# mcp3008_rpi_Dirty_july_2015.net
KiCad netlist of a schematic drawn in EAGLE
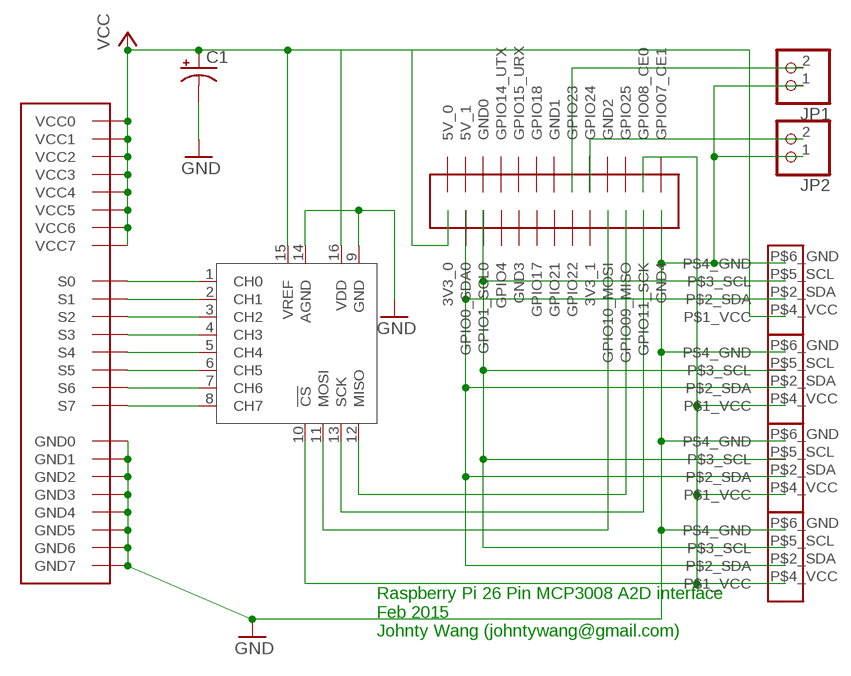
[diagram p0: schematic, sheet 1]

(export (version "E")
  (design (tool "Eeschema 10.0.6"))
  (components
    (comp (ref "C1")
      (value "CPOL-USE2.5-6")
      (footprint "eagle-import:E2,5-6")
      (libsource (lib "eagle-import") (part "CPOL-USE2.5-6"))
    )
    (comp (ref "JP1")
      (value "PINHD-1X2")
      (footprint "eagle-import:1X02")
      (libsource (lib "eagle-import") (part "PINHD-1X2"))
    )
    (comp (ref "JP2")
      (value "PINHD-1X2")
      (footprint "eagle-import:1X02")
      (libsource (lib "eagle-import") (part "PINHD-1X2"))
    )
    (comp (ref "U$1")
      (value "3BY83X8_SAMTEC")
      (footprint "eagle-import:3X8_PKG")
      (libsource (lib "eagle-import") (part "3BY83X8_SAMTEC"))
    )
    (comp (ref "U$2")
      (value "RPI_26")
      (footprint "eagle-import:RPI26")
      (libsource (lib "eagle-import") (part "RPI_26"))
    )
    (comp (ref "U$3")
      (value "MCP3008P")
      (footprint "eagle-import:DIL16")
      (libsource (lib "eagle-import") (part "MCP3008P"))
    )
    (comp (ref "U$4")
      (value "ICUBE_I2C")
      (footprint "eagle-import:2X3")
      (libsource (lib "eagle-import") (part "ICUBE_I2C"))
    )
    (comp (ref "U$5")
      (value "ICUBE_I2C")
      (footprint "eagle-import:2X3")
      (libsource (lib "eagle-import") (part "ICUBE_I2C"))
    )
    (comp (ref "U$6")
      (value "ICUBE_I2C")
      (footprint "eagle-import:2X3")
      (libsource (lib "eagle-import") (part "ICUBE_I2C"))
    )
    (comp (ref "U$7")
      (value "ICUBE_I2C")
      (footprint "eagle-import:2X3")
      (libsource (lib "eagle-import") (part "ICUBE_I2C"))
    )
  )
  (nets
    (net (code "1") (name "/5V_0") (class "Default")
      (node (ref "U$2") (pin "5V0") (pinfunction "5V_0_5V0") (pintype "power_in"))
    )
    (net (code "2") (name "GND") (class "Default")
      (node (ref "C1") (pin "-") (pinfunction "-_-") (pintype "passive"))
      (node (ref "JP1") (pin "1") (pinfunction "1_1") (pintype "passive"))
      (node (ref "JP2") (pin "1") (pinfunction "1_1") (pintype "passive"))
      (node (ref "U$1") (pin "GND0") (pinfunction "GND0_GND0") (pintype "bidirectional"))
      (node (ref "U$1") (pin "GND1") (pinfunction "GND1_GND1") (pintype "bidirectional"))
      (node (ref "U$1") (pin "GND2") (pinfunction "GND2_GND2") (pintype "bidirectional"))
      (node (ref "U$1") (pin "GND3") (pinfunction "GND3_GND3") (pintype "bidirectional"))
      (node (ref "U$1") (pin "GND4") (pinfunction "GND4_GND4") (pintype "bidirectional"))
      (node (ref "U$1") (pin "GND5") (pinfunction "GND5_GND5") (pintype "bidirectional"))
      (node (ref "U$1") (pin "GND6") (pinfunction "GND6_GND6") (pintype "bidirectional"))
      (node (ref "U$1") (pin "GND7") (pinfunction "GND7_GND7") (pintype "bidirectional"))
      (node (ref "U$2") (pin "GND4") (pinfunction "GND4_GND4") (pintype "bidirectional"))
      (node (ref "U$3") (pin "14") (pinfunction "AGND_14") (pintype "power_in"))
      (node (ref "U$3") (pin "9") (pinfunction "GND_9") (pintype "power_in"))
      (node (ref "U$4") (pin "P$6_GND") (pinfunction "P$4_GND_P$6_GND") (pintype "bidirectional"))
      (node (ref "U$5") (pin "P$6_GND") (pinfunction "P$4_GND_P$6_GND") (pintype "bidirectional"))
      (node (ref "U$6") (pin "P$6_GND") (pinfunction "P$4_GND_P$6_GND") (pintype "bidirectional"))
      (node (ref "U$7") (pin "P$6_GND") (pinfunction "P$4_GND_P$6_GND") (pintype "bidirectional"))
    )
    (net (code "3") (name "Net-(JP1-Pad2)") (class "Default")
      (node (ref "JP1") (pin "2") (pinfunction "2_2") (pintype "passive"))
      (node (ref "U$2") (pin "GPIO23") (pinfunction "GPIO23_GPIO23") (pintype "bidirectional"))
    )
    (net (code "4") (name "Net-(JP2-Pad2)") (class "Default")
      (node (ref "JP2") (pin "2") (pinfunction "2_2") (pintype "passive"))
      (node (ref "U$2") (pin "GPIO24") (pinfunction "GPIO24_GPIO24") (pintype "bidirectional"))
    )
    (net (code "5") (name "Net-(U$2-GPIO0_SDA0)") (class "Default")
      (node (ref "U$2") (pin "GPIO0") (pinfunction "GPIO0_SDA0_GPIO0") (pintype "bidirectional"))
      (node (ref "U$4") (pin "P$2_SDA") (pinfunction "P$2_SDA_P$2_SDA") (pintype "bidirectional"))
      (node (ref "U$5") (pin "P$2_SDA") (pinfunction "P$2_SDA_P$2_SDA") (pintype "bidirectional"))
      (node (ref "U$6") (pin "P$2_SDA") (pinfunction "P$2_SDA_P$2_SDA") (pintype "bidirectional"))
      (node (ref "U$7") (pin "P$2_SDA") (pinfunction "P$2_SDA_P$2_SDA") (pintype "bidirectional"))
    )
    (net (code "6") (name "Net-(U$2-GPIO1_SCL0)") (class "Default")
      (node (ref "U$2") (pin "GPIO01") (pinfunction "GPIO1_SCL0_GPIO01") (pintype "bidirectional"))
      (node (ref "U$4") (pin "P$5_SCL") (pinfunction "P$3_SCL_P$5_SCL") (pintype "bidirectional"))
      (node (ref "U$5") (pin "P$5_SCL") (pinfunction "P$3_SCL_P$5_SCL") (pintype "bidirectional"))
      (node (ref "U$6") (pin "P$5_SCL") (pinfunction "P$3_SCL_P$5_SCL") (pintype "bidirectional"))
      (node (ref "U$7") (pin "P$5_SCL") (pinfunction "P$3_SCL_P$5_SCL") (pintype "bidirectional"))
    )
    (net (code "7") (name "Net-(U$2-GPIO08_CE0)") (class "Default")
      (node (ref "U$2") (pin "GPIO08") (pinfunction "GPIO08_CE0_GPIO08") (pintype "bidirectional"))
      (node (ref "U$3") (pin "10") (pinfunction "~{CS}_10") (pintype "input"))
      (node (ref "U$5") (pin "P$4_VCC") (pinfunction "P$1_VCC_P$4_VCC") (pintype "bidirectional"))
      (node (ref "U$6") (pin "P$4_VCC") (pinfunction "P$1_VCC_P$4_VCC") (pintype "bidirectional"))
      (node (ref "U$7") (pin "P$4_VCC") (pinfunction "P$1_VCC_P$4_VCC") (pintype "bidirectional"))
    )
    (net (code "8") (name "Net-(U$2-GPIO09_MISO)") (class "Default")
      (node (ref "U$2") (pin "GPIO09") (pinfunction "GPIO09_MISO_GPIO09") (pintype "bidirectional"))
      (node (ref "U$3") (pin "12") (pinfunction "MISO_12") (pintype "output"))
    )
    (net (code "9") (name "Net-(U$2-GPIO10_MOSI)") (class "Default")
      (node (ref "U$2") (pin "GPIO10") (pinfunction "GPIO10_MOSI_GPIO10") (pintype "bidirectional"))
      (node (ref "U$3") (pin "11") (pinfunction "MOSI_11") (pintype "input"))
    )
    (net (code "10") (name "Net-(U$2-GPIO11_SCK)") (class "Default")
      (node (ref "U$2") (pin "GPIO11") (pinfunction "GPIO11_SCK_GPIO11") (pintype "bidirectional"))
      (node (ref "U$3") (pin "13") (pinfunction "SCK_13") (pintype "input"))
    )
    (net (code "11") (name "Net-(U$3-CH0)") (class "Default")
      (node (ref "U$1") (pin "S0") (pinfunction "S0_S0") (pintype "bidirectional"))
      (node (ref "U$3") (pin "1") (pinfunction "CH0_1") (pintype "input"))
    )
    (net (code "12") (name "Net-(U$3-CH1)") (class "Default")
      (node (ref "U$1") (pin "S1") (pinfunction "S1_S1") (pintype "bidirectional"))
      (node (ref "U$3") (pin "2") (pinfunction "CH1_2") (pintype "input"))
    )
    (net (code "13") (name "Net-(U$3-CH2)") (class "Default")
      (node (ref "U$1") (pin "S2") (pinfunction "S2_S2") (pintype "bidirectional"))
      (node (ref "U$3") (pin "3") (pinfunction "CH2_3") (pintype "input"))
    )
    (net (code "14") (name "Net-(U$3-CH3)") (class "Default")
      (node (ref "U$1") (pin "S3") (pinfunction "S3_S3") (pintype "bidirectional"))
      (node (ref "U$3") (pin "4") (pinfunction "CH3_4") (pintype "input"))
    )
    (net (code "15") (name "Net-(U$3-CH4)") (class "Default")
      (node (ref "U$1") (pin "S4") (pinfunction "S4_S4") (pintype "bidirectional"))
      (node (ref "U$3") (pin "5") (pinfunction "CH4_5") (pintype "input"))
    )
    (net (code "16") (name "Net-(U$3-CH5)") (class "Default")
      (node (ref "U$1") (pin "S5") (pinfunction "S5_S5") (pintype "bidirectional"))
      (node (ref "U$3") (pin "6") (pinfunction "CH5_6") (pintype "input"))
    )
    (net (code "17") (name "Net-(U$3-CH6)") (class "Default")
      (node (ref "U$1") (pin "S6") (pinfunction "S6_S6") (pintype "bidirectional"))
      (node (ref "U$3") (pin "7") (pinfunction "CH6_7") (pintype "input"))
    )
    (net (code "18") (name "Net-(U$3-CH7)") (class "Default")
      (node (ref "U$1") (pin "S7") (pinfunction "S7_S7") (pintype "bidirectional"))
      (node (ref "U$3") (pin "8") (pinfunction "CH7_8") (pintype "input"))
    )
    (net (code "19") (name "VCC") (class "Default")
      (node (ref "C1") (pin "+") (pinfunction "+_+") (pintype "passive"))
      (node (ref "U$1") (pin "VCC0") (pinfunction "VCC0_VCC0") (pintype "bidirectional"))
      (node (ref "U$1") (pin "VCC1") (pinfunction "VCC1_VCC1") (pintype "bidirectional"))
      (node (ref "U$1") (pin "VCC2") (pinfunction "VCC2_VCC2") (pintype "bidirectional"))
      (node (ref "U$1") (pin "VCC3") (pinfunction "VCC3_VCC3") (pintype "bidirectional"))
      (node (ref "U$1") (pin "VCC4") (pinfunction "VCC4_VCC4") (pintype "bidirectional"))
      (node (ref "U$1") (pin "VCC5") (pinfunction "VCC5_VCC5") (pintype "bidirectional"))
      (node (ref "U$1") (pin "VCC6") (pinfunction "VCC6_VCC6") (pintype "bidirectional"))
      (node (ref "U$1") (pin "VCC7") (pinfunction "VCC7_VCC7") (pintype "bidirectional"))
      (node (ref "U$2") (pin "3V3_0") (pinfunction "3V3_0_3V3_0") (pintype "bidirectional"))
      (node (ref "U$3") (pin "15") (pinfunction "VREF_15") (pintype "power_in"))
      (node (ref "U$3") (pin "16") (pinfunction "VDD_16") (pintype "power_in"))
      (node (ref "U$4") (pin "P$4_VCC") (pinfunction "P$1_VCC_P$4_VCC") (pintype "bidirectional"))
    )
    (net (code "20") (name "unconnected-(U$2-5V_1-Pad5V1)") (class "Default")
      (node (ref "U$2") (pin "5V1") (pinfunction "5V_1_5V1") (pintype "bidirectional"))
    )
    (net (code "21") (name "unconnected-(U$2-GPIO4-PadGPIO04)") (class "Default")
      (node (ref "U$2") (pin "GPIO04") (pinfunction "GPIO4_GPIO04") (pintype "bidirectional"))
    )
    (net (code "22") (name "unconnected-(U$2-GPIO07_CE1-PadGPIO07)") (class "Default")
      (node (ref "U$2") (pin "GPIO07") (pinfunction "GPIO07_CE1_GPIO07") (pintype "bidirectional"))
    )
    (net (code "23") (name "unconnected-(U$2-GPIO14_UTX-PadGPIO14)") (class "Default")
      (node (ref "U$2") (pin "GPIO14") (pinfunction "GPIO14_UTX_GPIO14") (pintype "bidirectional"))
    )
    (net (code "24") (name "unconnected-(U$2-GPIO15_URX-PadGPIO15)") (class "Default")
      (node (ref "U$2") (pin "GPIO15") (pinfunction "GPIO15_URX_GPIO15") (pintype "bidirectional"))
    )
    (net (code "25") (name "unconnected-(U$2-Pad3V3_1)") (class "Default")
      (node (ref "U$2") (pin "3V3_1") (pinfunction "3V3_1_3V3_1") (pintype "bidirectional"))
    )
    (net (code "26") (name "unconnected-(U$2-PadGND0)") (class "Default")
      (node (ref "U$2") (pin "GND0") (pinfunction "GND0_GND0") (pintype "bidirectional"))
    )
    (net (code "27") (name "unconnected-(U$2-PadGND1)") (class "Default")
      (node (ref "U$2") (pin "GND1") (pinfunction "GND1_GND1") (pintype "bidirectional"))
    )
    (net (code "28") (name "unconnected-(U$2-PadGND2)") (class "Default")
      (node (ref "U$2") (pin "GND2") (pinfunction "GND2_GND2") (pintype "bidirectional"))
    )
    (net (code "29") (name "unconnected-(U$2-PadGND3)") (class "Default")
      (node (ref "U$2") (pin "GND3") (pinfunction "GND3_GND3") (pintype "bidirectional"))
    )
    (net (code "30") (name "unconnected-(U$2-PadGPIO17)") (class "Default")
      (node (ref "U$2") (pin "GPIO17") (pinfunction "GPIO17_GPIO17") (pintype "bidirectional"))
    )
    (net (code "31") (name "unconnected-(U$2-PadGPIO18)") (class "Default")
      (node (ref "U$2") (pin "GPIO18") (pinfunction "GPIO18_GPIO18") (pintype "bidirectional"))
    )
    (net (code "32") (name "unconnected-(U$2-PadGPIO21)") (class "Default")
      (node (ref "U$2") (pin "GPIO21") (pinfunction "GPIO21_GPIO21") (pintype "bidirectional"))
    )
    (net (code "33") (name "unconnected-(U$2-PadGPIO22)") (class "Default")
      (node (ref "U$2") (pin "GPIO22") (pinfunction "GPIO22_GPIO22") (pintype "bidirectional"))
    )
    (net (code "34") (name "unconnected-(U$2-PadGPIO25)") (class "Default")
      (node (ref "U$2") (pin "GPIO25") (pinfunction "GPIO25_GPIO25") (pintype "bidirectional"))
    )
  )
)
